# LocalElectricCircuit.net
KiCad netlist of a schematic drawn in EAGLE
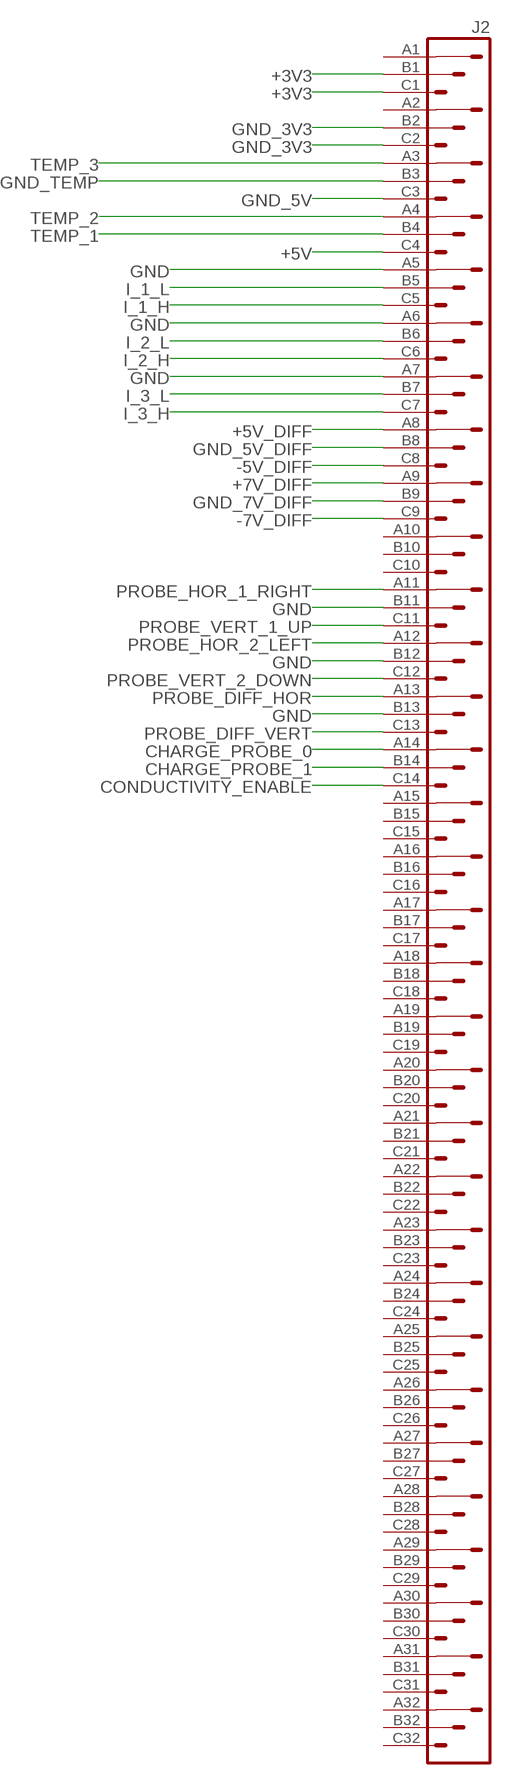
[diagram p0: schematic, sheet 1, part 1 of 2]
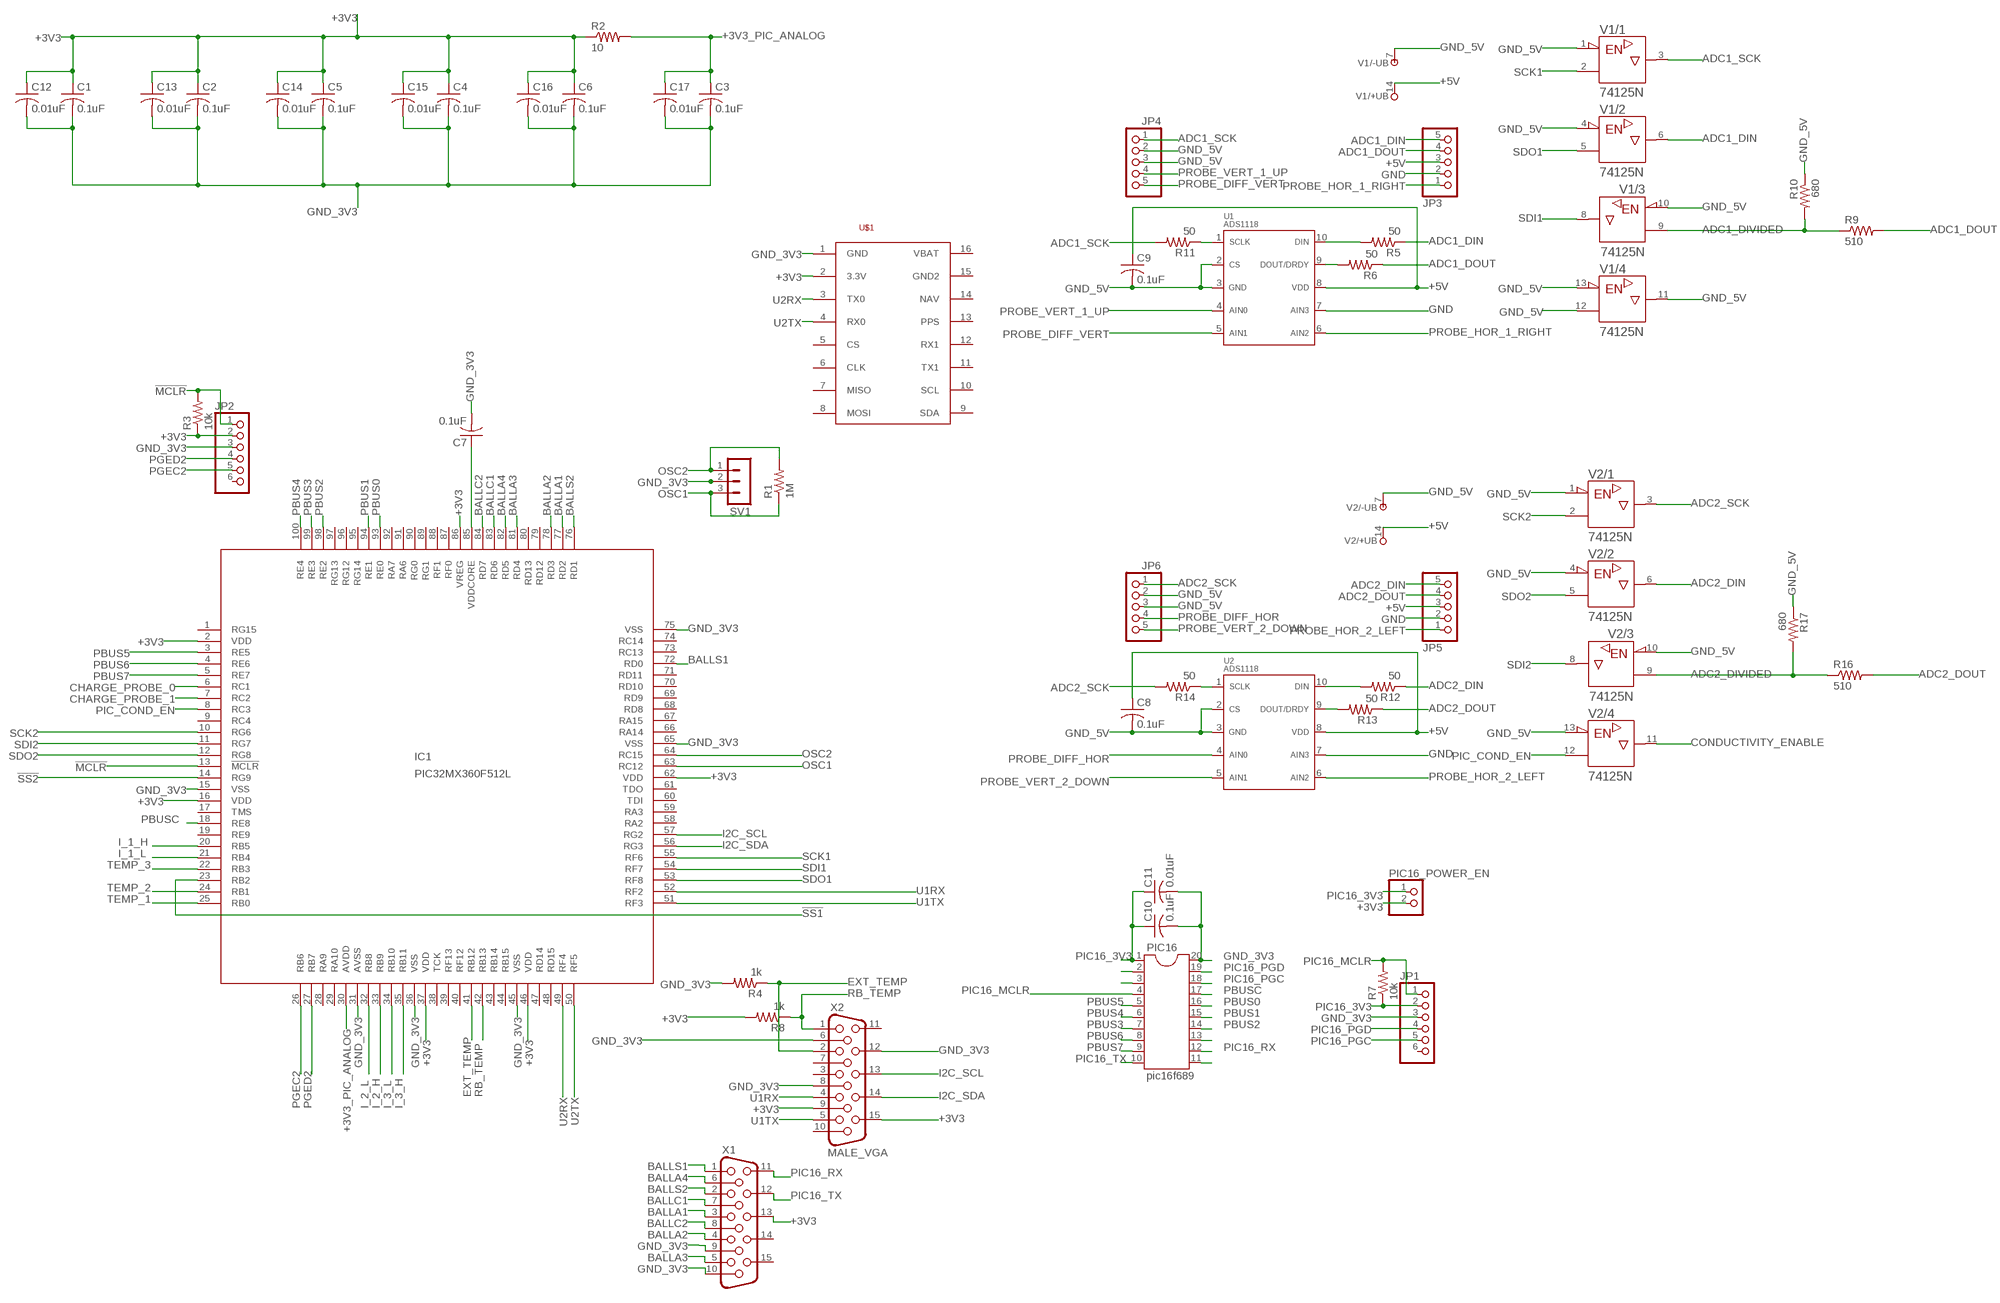
[diagram p1: schematic, sheet 1, part 2 of 2]

(export (version "E")
  (design (tool "Eeschema 10.0.6"))
  (components
    (comp (ref "C1")
      (value "0.1uF")
      (footprint "eagle-import:C1206")
      (libsource (lib "eagle-import") (part "C-USC1206"))
    )
    (comp (ref "C2")
      (value "0.1uF")
      (footprint "eagle-import:C1206")
      (libsource (lib "eagle-import") (part "C-USC1206"))
    )
    (comp (ref "C3")
      (value "0.1uF")
      (footprint "eagle-import:C1206")
      (libsource (lib "eagle-import") (part "C-USC1206"))
    )
    (comp (ref "C4")
      (value "0.1uF")
      (footprint "eagle-import:C1206")
      (libsource (lib "eagle-import") (part "C-USC1206"))
    )
    (comp (ref "C5")
      (value "0.1uF")
      (footprint "eagle-import:C1206")
      (libsource (lib "eagle-import") (part "C-USC1206"))
    )
    (comp (ref "C6")
      (value "0.1uF")
      (footprint "eagle-import:C1206")
      (libsource (lib "eagle-import") (part "C-USC1206"))
    )
    (comp (ref "C7")
      (value "0.1uF")
      (footprint "eagle-import:C1206")
      (libsource (lib "eagle-import") (part "C-USC1206"))
    )
    (comp (ref "C8")
      (value "0.1uF")
      (footprint "eagle-import:C1206")
      (libsource (lib "eagle-import") (part "C-USC1206"))
    )
    (comp (ref "C9")
      (value "0.1uF")
      (footprint "eagle-import:C1206")
      (libsource (lib "eagle-import") (part "C-USC1206"))
    )
    (comp (ref "C10")
      (value "0.1uF")
      (footprint "eagle-import:C1206")
      (libsource (lib "eagle-import") (part "C-USC1206"))
    )
    (comp (ref "C11")
      (value "0.01uF")
      (footprint "eagle-import:C1206")
      (libsource (lib "eagle-import") (part "C-USC1206"))
    )
    (comp (ref "C12")
      (value "0.01uF")
      (footprint "eagle-import:C1206")
      (libsource (lib "eagle-import") (part "C-USC1206"))
    )
    (comp (ref "C13")
      (value "0.01uF")
      (footprint "eagle-import:C1206")
      (libsource (lib "eagle-import") (part "C-USC1206"))
    )
    (comp (ref "C14")
      (value "0.01uF")
      (footprint "eagle-import:C1206")
      (libsource (lib "eagle-import") (part "C-USC1206"))
    )
    (comp (ref "C15")
      (value "0.01uF")
      (footprint "eagle-import:C1206")
      (libsource (lib "eagle-import") (part "C-USC1206"))
    )
    (comp (ref "C16")
      (value "0.01uF")
      (footprint "eagle-import:C1206")
      (libsource (lib "eagle-import") (part "C-USC1206"))
    )
    (comp (ref "C17")
      (value "0.01uF")
      (footprint "eagle-import:C1206")
      (libsource (lib "eagle-import") (part "C-USC1206"))
    )
    (comp (ref "IC1")
      (value "PIC32MX360F512L")
      (footprint "eagle-import:TQFP100")
      (libsource (lib "eagle-import") (part "PIC32MX360F512L"))
    )
    (comp (ref "J2")
      (value "VG96KB")
      (footprint "eagle-import:VG96KB")
      (libsource (lib "eagle-import") (part "VG96KB"))
    )
    (comp (ref "JP1")
      (value "PINHD-1X6")
      (footprint "eagle-import:1X06")
      (libsource (lib "eagle-import") (part "PINHD-1X6"))
    )
    (comp (ref "JP2")
      (value "PINHD-1X6")
      (footprint "eagle-import:1X06")
      (libsource (lib "eagle-import") (part "PINHD-1X6"))
    )
    (comp (ref "JP3")
      (value "PINHD-1X5")
      (footprint "eagle-import:1X05")
      (libsource (lib "eagle-import") (part "PINHD-1X5"))
    )
    (comp (ref "JP4")
      (value "PINHD-1X5")
      (footprint "eagle-import:1X05")
      (libsource (lib "eagle-import") (part "PINHD-1X5"))
    )
    (comp (ref "JP5")
      (value "PINHD-1X5")
      (footprint "eagle-import:1X05")
      (libsource (lib "eagle-import") (part "PINHD-1X5"))
    )
    (comp (ref "JP6")
      (value "PINHD-1X5")
      (footprint "eagle-import:1X05")
      (libsource (lib "eagle-import") (part "PINHD-1X5"))
    )
    (comp (ref "PIC16")
      (value "pic16f689")
      (footprint "eagle-import:DIL20")
      (libsource (lib "eagle-import") (part "DIL20"))
    )
    (comp (ref "PIC16_POWER_EN")
      (value "PINHD-1X2")
      (footprint "eagle-import:1X02")
      (libsource (lib "eagle-import") (part "PINHD-1X2"))
    )
    (comp (ref "R1")
      (value "1M")
      (footprint "eagle-import:M1206")
      (libsource (lib "eagle-import") (part "R-US_M1206"))
    )
    (comp (ref "R2")
      (value "10")
      (footprint "eagle-import:M1206")
      (libsource (lib "eagle-import") (part "R-US_M1206"))
    )
    (comp (ref "R3")
      (value "10k")
      (footprint "eagle-import:M1206")
      (libsource (lib "eagle-import") (part "R-US_M1206"))
    )
    (comp (ref "R4")
      (value "1k")
      (footprint "eagle-import:0414_15")
      (libsource (lib "eagle-import") (part "resistor_R-US_0414/15"))
    )
    (comp (ref "R5")
      (value "50")
      (footprint "eagle-import:M1206")
      (libsource (lib "eagle-import") (part "R-US_M1206"))
    )
    (comp (ref "R6")
      (value "50")
      (footprint "eagle-import:M1206")
      (libsource (lib "eagle-import") (part "R-US_M1206"))
    )
    (comp (ref "R7")
      (value "10k")
      (footprint "eagle-import:M1206")
      (libsource (lib "eagle-import") (part "R-US_M1206"))
    )
    (comp (ref "R8")
      (value "1k")
      (footprint "eagle-import:0414_15")
      (libsource (lib "eagle-import") (part "resistor_R-US_0414/15"))
    )
    (comp (ref "R9")
      (value "510")
      (footprint "eagle-import:R1206")
      (libsource (lib "eagle-import") (part "resistor_R-US_R1206"))
    )
    (comp (ref "R10")
      (value "680")
      (footprint "eagle-import:R1206")
      (libsource (lib "eagle-import") (part "resistor_R-US_R1206"))
    )
    (comp (ref "R11")
      (value "50")
      (footprint "eagle-import:M1206")
      (libsource (lib "eagle-import") (part "R-US_M1206"))
    )
    (comp (ref "R12")
      (value "50")
      (footprint "eagle-import:M1206")
      (libsource (lib "eagle-import") (part "R-US_M1206"))
    )
    (comp (ref "R13")
      (value "50")
      (footprint "eagle-import:M1206")
      (libsource (lib "eagle-import") (part "R-US_M1206"))
    )
    (comp (ref "R14")
      (value "50")
      (footprint "eagle-import:M1206")
      (libsource (lib "eagle-import") (part "R-US_M1206"))
    )
    (comp (ref "R16")
      (value "510")
      (footprint "eagle-import:R1206")
      (libsource (lib "eagle-import") (part "resistor_R-US_R1206"))
    )
    (comp (ref "R17")
      (value "680")
      (footprint "eagle-import:R1206")
      (libsource (lib "eagle-import") (part "resistor_R-US_R1206"))
    )
    (comp (ref "SV1")
      (value "MA03-1")
      (footprint "eagle-import:MA03-1")
      (libsource (lib "eagle-import") (part "MA03-1"))
    )
    (comp (ref "U$1")
      (value "SPARKFUN_VENUS_GPS_BREAKOUT")
      (footprint "eagle-import:SPARKFUN_BOARD")
      (libsource (lib "eagle-import") (part "SPARKFUN_VENUS_GPS_BREAKOUT"))
    )
    (comp (ref "U1")
      (value "ADS1118")
      (footprint "eagle-import:MSOP10")
      (libsource (lib "eagle-import") (part "ADS1118_MSOP10"))
    )
    (comp (ref "U2")
      (value "ADS1118")
      (footprint "eagle-import:MSOP10")
      (libsource (lib "eagle-import") (part "ADS1118_MSOP10"))
    )
    (comp (ref "V1")
      (value "74125N")
      (footprint "eagle-import:DIL14")
      (libsource (lib "eagle-import") (part "74125N"))
    )
    (comp (ref "V2")
      (value "74125N")
      (footprint "eagle-import:DIL14")
      (libsource (lib "eagle-import") (part "74125N"))
    )
    (comp (ref "X1")
      (value "HF15H")
      (footprint "eagle-import:HDF15H")
      (libsource (lib "eagle-import") (part "HF15H"))
    )
    (comp (ref "X2")
      (value "MALE_VGA")
      (footprint "eagle-import:MALE_PACKAGE")
      (libsource (lib "eagle-import") (part "MALE_VGA"))
    )
  )
  (nets
    (net (code "1") (name "/+3V3") (class "Default")
      (node (ref "C1") (pin "1") (pinfunction "1_1") (pintype "passive"))
      (node (ref "C12") (pin "1") (pinfunction "1_1") (pintype "passive"))
      (node (ref "C13") (pin "1") (pinfunction "1_1") (pintype "passive"))
      (node (ref "C14") (pin "1") (pinfunction "1_1") (pintype "passive"))
      (node (ref "C15") (pin "1") (pinfunction "1_1") (pintype "passive"))
      (node (ref "C16") (pin "1") (pinfunction "1_1") (pintype "passive"))
      (node (ref "C2") (pin "1") (pinfunction "1_1") (pintype "passive"))
      (node (ref "C4") (pin "1") (pinfunction "1_1") (pintype "passive"))
      (node (ref "C5") (pin "1") (pinfunction "1_1") (pintype "passive"))
      (node (ref "C6") (pin "1") (pinfunction "1_1") (pintype "passive"))
      (node (ref "IC1") (pin "16") (pinfunction "VDD_16") (pintype "power_in"))
      (node (ref "IC1") (pin "2") (pinfunction "VDD_2") (pintype "power_in"))
      (node (ref "IC1") (pin "37") (pinfunction "VDD_37") (pintype "power_in"))
      (node (ref "IC1") (pin "46") (pinfunction "VDD_46") (pintype "power_in"))
      (node (ref "IC1") (pin "62") (pinfunction "VDD_62") (pintype "power_in"))
      (node (ref "IC1") (pin "86") (pinfunction "VREG_86") (pintype "passive"))
      (node (ref "J2") (pin "B1") (pinfunction "B1_B1") (pintype "passive"))
      (node (ref "J2") (pin "C1") (pinfunction "C1_C1") (pintype "passive"))
      (node (ref "JP2") (pin "2") (pinfunction "2_2") (pintype "passive"))
      (node (ref "PIC16_POWER_EN") (pin "2") (pinfunction "2_2") (pintype "passive"))
      (node (ref "R2") (pin "1") (pinfunction "1_1") (pintype "passive"))
      (node (ref "R3") (pin "1") (pinfunction "1_1") (pintype "passive"))
      (node (ref "R8") (pin "2") (pinfunction "2_2") (pintype "passive"))
      (node (ref "U$1") (pin "2") (pinfunction "3.3V_2") (pintype "bidirectional"))
      (node (ref "X1") (pin "13") (pinfunction "13_13") (pintype "passive"))
      (node (ref "X2") (pin "15") (pinfunction "15_15") (pintype "passive"))
      (node (ref "X2") (pin "9") (pinfunction "9_9") (pintype "passive"))
    )
    (net (code "2") (name "/+3V3_PIC_ANALOG") (class "Default")
      (node (ref "C17") (pin "1") (pinfunction "1_1") (pintype "passive"))
      (node (ref "C3") (pin "1") (pinfunction "1_1") (pintype "passive"))
      (node (ref "IC1") (pin "30") (pinfunction "AVDD_30") (pintype "power_in"))
      (node (ref "R2") (pin "2") (pinfunction "2_2") (pintype "passive"))
    )
    (net (code "3") (name "/+5V") (class "Default")
      (node (ref "C8") (pin "1") (pinfunction "1_1") (pintype "passive"))
      (node (ref "C9") (pin "1") (pinfunction "1_1") (pintype "passive"))
      (node (ref "J2") (pin "C4") (pinfunction "C4_C4") (pintype "passive"))
      (node (ref "JP3") (pin "3") (pinfunction "3_3") (pintype "passive"))
      (node (ref "JP5") (pin "3") (pinfunction "3_3") (pintype "passive"))
      (node (ref "U1") (pin "8") (pinfunction "VDD_8") (pintype "bidirectional"))
      (node (ref "U2") (pin "8") (pinfunction "VDD_8") (pintype "bidirectional"))
      (node (ref "V1") (pin "14") (pinfunction "+UB_14") (pintype "power_in"))
      (node (ref "V2") (pin "14") (pinfunction "+UB_14") (pintype "power_in"))
    )
    (net (code "4") (name "/+5V_DIFF") (class "Default")
      (node (ref "J2") (pin "A8") (pinfunction "A8_A8") (pintype "passive"))
    )
    (net (code "5") (name "/+7V_DIFF") (class "Default")
      (node (ref "J2") (pin "A9") (pinfunction "A9_A9") (pintype "passive"))
    )
    (net (code "6") (name "/-5V_DIFF") (class "Default")
      (node (ref "J2") (pin "C8") (pinfunction "C8_C8") (pintype "passive"))
    )
    (net (code "7") (name "/-7V_DIFF") (class "Default")
      (node (ref "J2") (pin "C9") (pinfunction "C9_C9") (pintype "passive"))
    )
    (net (code "8") (name "/ADC1_DIN") (class "Default")
      (node (ref "JP3") (pin "5") (pinfunction "5_5") (pintype "passive"))
      (node (ref "R5") (pin "1") (pinfunction "1_1") (pintype "passive"))
      (node (ref "V1") (pin "6") (pinfunction "Y_6") (pintype "tri_state"))
    )
    (net (code "9") (name "/ADC1_DIVIDED") (class "Default")
      (node (ref "R10") (pin "2") (pinfunction "2_2") (pintype "passive"))
      (node (ref "R9") (pin "1") (pinfunction "1_1") (pintype "passive"))
      (node (ref "V1") (pin "9") (pinfunction "A_9") (pintype "input"))
    )
    (net (code "10") (name "/ADC1_DOUT") (class "Default")
      (node (ref "JP3") (pin "4") (pinfunction "4_4") (pintype "passive"))
      (node (ref "R6") (pin "1") (pinfunction "1_1") (pintype "passive"))
      (node (ref "R9") (pin "2") (pinfunction "2_2") (pintype "passive"))
    )
    (net (code "11") (name "/ADC1_SCK") (class "Default")
      (node (ref "JP4") (pin "1") (pinfunction "1_1") (pintype "passive"))
      (node (ref "R11") (pin "2") (pinfunction "2_2") (pintype "passive"))
      (node (ref "V1") (pin "3") (pinfunction "Y_3") (pintype "tri_state"))
    )
    (net (code "12") (name "/ADC2_DIN") (class "Default")
      (node (ref "JP5") (pin "5") (pinfunction "5_5") (pintype "passive"))
      (node (ref "R12") (pin "1") (pinfunction "1_1") (pintype "passive"))
      (node (ref "V2") (pin "6") (pinfunction "Y_6") (pintype "tri_state"))
    )
    (net (code "13") (name "/ADC2_DIVIDED") (class "Default")
      (node (ref "R16") (pin "1") (pinfunction "1_1") (pintype "passive"))
      (node (ref "R17") (pin "2") (pinfunction "2_2") (pintype "passive"))
      (node (ref "V2") (pin "9") (pinfunction "A_9") (pintype "input"))
    )
    (net (code "14") (name "/ADC2_DOUT") (class "Default")
      (node (ref "JP5") (pin "4") (pinfunction "4_4") (pintype "passive"))
      (node (ref "R13") (pin "1") (pinfunction "1_1") (pintype "passive"))
      (node (ref "R16") (pin "2") (pinfunction "2_2") (pintype "passive"))
    )
    (net (code "15") (name "/ADC2_SCK") (class "Default")
      (node (ref "JP6") (pin "1") (pinfunction "1_1") (pintype "passive"))
      (node (ref "R14") (pin "2") (pinfunction "2_2") (pintype "passive"))
      (node (ref "V2") (pin "3") (pinfunction "Y_3") (pintype "tri_state"))
    )
    (net (code "16") (name "/BALLA1") (class "Default")
      (node (ref "IC1") (pin "77") (pinfunction "RD2_77") (pintype "bidirectional"))
      (node (ref "X1") (pin "3") (pinfunction "3_3") (pintype "passive"))
    )
    (net (code "17") (name "/BALLA2") (class "Default")
      (node (ref "IC1") (pin "78") (pinfunction "RD3_78") (pintype "bidirectional"))
      (node (ref "X1") (pin "4") (pinfunction "4_4") (pintype "passive"))
    )
    (net (code "18") (name "/BALLA3") (class "Default")
      (node (ref "IC1") (pin "81") (pinfunction "RD4_81") (pintype "bidirectional"))
      (node (ref "X1") (pin "5") (pinfunction "5_5") (pintype "passive"))
    )
    (net (code "19") (name "/BALLA4") (class "Default")
      (node (ref "IC1") (pin "82") (pinfunction "RD5_82") (pintype "bidirectional"))
      (node (ref "X1") (pin "6") (pinfunction "6_6") (pintype "passive"))
    )
    (net (code "20") (name "/BALLC1") (class "Default")
      (node (ref "IC1") (pin "83") (pinfunction "RD6_83") (pintype "bidirectional"))
      (node (ref "X1") (pin "7") (pinfunction "7_7") (pintype "passive"))
    )
    (net (code "21") (name "/BALLC2") (class "Default")
      (node (ref "IC1") (pin "84") (pinfunction "RD7_84") (pintype "bidirectional"))
      (node (ref "X1") (pin "8") (pinfunction "8_8") (pintype "passive"))
    )
    (net (code "22") (name "/BALLS1") (class "Default")
      (node (ref "IC1") (pin "72") (pinfunction "RD0_72") (pintype "bidirectional"))
      (node (ref "X1") (pin "1") (pinfunction "1_1") (pintype "passive"))
    )
    (net (code "23") (name "/BALLS2") (class "Default")
      (node (ref "IC1") (pin "76") (pinfunction "RD1_76") (pintype "bidirectional"))
      (node (ref "X1") (pin "2") (pinfunction "2_2") (pintype "passive"))
    )
    (net (code "24") (name "/CHARGE_PROBE_0") (class "Default")
      (node (ref "IC1") (pin "6") (pinfunction "RC1_6") (pintype "bidirectional"))
      (node (ref "J2") (pin "A14") (pinfunction "A14_A14") (pintype "passive"))
    )
    (net (code "25") (name "/CHARGE_PROBE_1") (class "Default")
      (node (ref "IC1") (pin "7") (pinfunction "RC2_7") (pintype "bidirectional"))
      (node (ref "J2") (pin "B14") (pinfunction "B14_B14") (pintype "passive"))
    )
    (net (code "26") (name "/CONDUCTIVITY_ENABLE") (class "Default")
      (node (ref "J2") (pin "C14") (pinfunction "C14_C14") (pintype "passive"))
      (node (ref "V2") (pin "11") (pinfunction "Y_11") (pintype "tri_state"))
    )
    (net (code "27") (name "/EXT_TEMP") (class "Default")
      (node (ref "IC1") (pin "41") (pinfunction "RB12_41") (pintype "bidirectional"))
      (node (ref "R4") (pin "1") (pinfunction "1_1") (pintype "passive"))
      (node (ref "X2") (pin "2") (pinfunction "2_2") (pintype "passive"))
    )
    (net (code "28") (name "/GND") (class "Default")
      (node (ref "J2") (pin "A5") (pinfunction "A5_A5") (pintype "passive"))
      (node (ref "J2") (pin "A6") (pinfunction "A6_A6") (pintype "passive"))
      (node (ref "J2") (pin "A7") (pinfunction "A7_A7") (pintype "passive"))
      (node (ref "J2") (pin "B11") (pinfunction "B11_B11") (pintype "passive"))
      (node (ref "J2") (pin "B12") (pinfunction "B12_B12") (pintype "passive"))
      (node (ref "J2") (pin "B13") (pinfunction "B13_B13") (pintype "passive"))
      (node (ref "JP3") (pin "2") (pinfunction "2_2") (pintype "passive"))
      (node (ref "JP5") (pin "2") (pinfunction "2_2") (pintype "passive"))
      (node (ref "U1") (pin "7") (pinfunction "AIN3_7") (pintype "bidirectional"))
      (node (ref "U2") (pin "7") (pinfunction "AIN3_7") (pintype "bidirectional"))
    )
    (net (code "29") (name "/GND_3V3") (class "Default")
      (node (ref "C1") (pin "2") (pinfunction "2_2") (pintype "passive"))
      (node (ref "C10") (pin "2") (pinfunction "2_2") (pintype "passive"))
      (node (ref "C11") (pin "2") (pinfunction "2_2") (pintype "passive"))
      (node (ref "C12") (pin "2") (pinfunction "2_2") (pintype "passive"))
      (node (ref "C13") (pin "2") (pinfunction "2_2") (pintype "passive"))
      (node (ref "C14") (pin "2") (pinfunction "2_2") (pintype "passive"))
      (node (ref "C15") (pin "2") (pinfunction "2_2") (pintype "passive"))
      (node (ref "C16") (pin "2") (pinfunction "2_2") (pintype "passive"))
      (node (ref "C17") (pin "2") (pinfunction "2_2") (pintype "passive"))
      (node (ref "C2") (pin "2") (pinfunction "2_2") (pintype "passive"))
      (node (ref "C3") (pin "2") (pinfunction "2_2") (pintype "passive"))
      (node (ref "C4") (pin "2") (pinfunction "2_2") (pintype "passive"))
      (node (ref "C5") (pin "2") (pinfunction "2_2") (pintype "passive"))
      (node (ref "C6") (pin "2") (pinfunction "2_2") (pintype "passive"))
      (node (ref "C7") (pin "2") (pinfunction "2_2") (pintype "passive"))
      (node (ref "IC1") (pin "15") (pinfunction "VSS_15") (pintype "power_in"))
      (node (ref "IC1") (pin "31") (pinfunction "AVSS_31") (pintype "power_in"))
      (node (ref "IC1") (pin "36") (pinfunction "VSS_36") (pintype "power_in"))
      (node (ref "IC1") (pin "45") (pinfunction "VSS_45") (pintype "power_in"))
      (node (ref "IC1") (pin "65") (pinfunction "VSS_65") (pintype "power_in"))
      (node (ref "IC1") (pin "75") (pinfunction "VSS_75") (pintype "power_in"))
      (node (ref "J2") (pin "B2") (pinfunction "B2_B2") (pintype "passive"))
      (node (ref "J2") (pin "C2") (pinfunction "C2_C2") (pintype "passive"))
      (node (ref "JP1") (pin "3") (pinfunction "3_3") (pintype "passive"))
      (node (ref "JP2") (pin "3") (pinfunction "3_3") (pintype "passive"))
      (node (ref "PIC16") (pin "20") (pinfunction "20_20") (pintype "passive"))
      (node (ref "R4") (pin "2") (pinfunction "2_2") (pintype "passive"))
      (node (ref "SV1") (pin "2") (pinfunction "2_2") (pintype "passive"))
      (node (ref "U$1") (pin "1") (pinfunction "GND_1") (pintype "bidirectional"))
      (node (ref "X1") (pin "10") (pinfunction "10_10") (pintype "passive"))
      (node (ref "X1") (pin "9") (pinfunction "9_9") (pintype "passive"))
      (node (ref "X2") (pin "12") (pinfunction "12_12") (pintype "passive"))
      (node (ref "X2") (pin "6") (pinfunction "6_6") (pintype "passive"))
      (node (ref "X2") (pin "8") (pinfunction "8_8") (pintype "passive"))
    )
    (net (code "30") (name "/GND_5V") (class "Default")
      (node (ref "C8") (pin "2") (pinfunction "2_2") (pintype "passive"))
      (node (ref "C9") (pin "2") (pinfunction "2_2") (pintype "passive"))
      (node (ref "J2") (pin "C3") (pinfunction "C3_C3") (pintype "passive"))
      (node (ref "JP4") (pin "2") (pinfunction "2_2") (pintype "passive"))
      (node (ref "JP4") (pin "3") (pinfunction "3_3") (pintype "passive"))
      (node (ref "JP6") (pin "2") (pinfunction "2_2") (pintype "passive"))
      (node (ref "JP6") (pin "3") (pinfunction "3_3") (pintype "passive"))
      (node (ref "R10") (pin "1") (pinfunction "1_1") (pintype "passive"))
      (node (ref "R17") (pin "1") (pinfunction "1_1") (pintype "passive"))
      (node (ref "U1") (pin "2") (pinfunction "CS_2") (pintype "bidirectional"))
      (node (ref "U1") (pin "3") (pinfunction "GND_3") (pintype "bidirectional"))
      (node (ref "U2") (pin "2") (pinfunction "CS_2") (pintype "bidirectional"))
      (node (ref "U2") (pin "3") (pinfunction "GND_3") (pintype "bidirectional"))
      (node (ref "V1") (pin "1") (pinfunction "~{G}_1") (pintype "input"))
      (node (ref "V1") (pin "10") (pinfunction "~{G}_10") (pintype "input"))
      (node (ref "V1") (pin "11") (pinfunction "Y_11") (pintype "tri_state"))
      (node (ref "V1") (pin "12") (pinfunction "A_12") (pintype "input"))
      (node (ref "V1") (pin "13") (pinfunction "~{G}_13") (pintype "input"))
      (node (ref "V1") (pin "4") (pinfunction "~{G}_4") (pintype "input"))
      (node (ref "V1") (pin "7") (pinfunction "-UB_7") (pintype "power_in"))
      (node (ref "V2") (pin "1") (pinfunction "~{G}_1") (pintype "input"))
      (node (ref "V2") (pin "10") (pinfunction "~{G}_10") (pintype "input"))
      (node (ref "V2") (pin "13") (pinfunction "~{G}_13") (pintype "input"))
      (node (ref "V2") (pin "4") (pinfunction "~{G}_4") (pintype "input"))
      (node (ref "V2") (pin "7") (pinfunction "-UB_7") (pintype "power_in"))
    )
    (net (code "31") (name "/GND_5V_DIFF") (class "Default")
      (node (ref "J2") (pin "B8") (pinfunction "B8_B8") (pintype "passive"))
    )
    (net (code "32") (name "/GND_7V_DIFF") (class "Default")
      (node (ref "J2") (pin "B9") (pinfunction "B9_B9") (pintype "passive"))
    )
    (net (code "33") (name "/GND_TEMP") (class "Default")
      (node (ref "J2") (pin "B3") (pinfunction "B3_B3") (pintype "passive"))
    )
    (net (code "34") (name "/I2C_SCL") (class "Default")
      (node (ref "IC1") (pin "57") (pinfunction "RG2_57") (pintype "bidirectional"))
      (node (ref "X2") (pin "13") (pinfunction "13_13") (pintype "passive"))
    )
    (net (code "35") (name "/I2C_SDA") (class "Default")
      (node (ref "IC1") (pin "56") (pinfunction "RG3_56") (pintype "bidirectional"))
      (node (ref "X2") (pin "14") (pinfunction "14_14") (pintype "passive"))
    )
    (net (code "36") (name "/I_1_H") (class "Default")
      (node (ref "IC1") (pin "20") (pinfunction "RB5_20") (pintype "bidirectional"))
      (node (ref "J2") (pin "C5") (pinfunction "C5_C5") (pintype "passive"))
    )
    (net (code "37") (name "/I_1_L") (class "Default")
      (node (ref "IC1") (pin "21") (pinfunction "RB4_21") (pintype "bidirectional"))
      (node (ref "J2") (pin "B5") (pinfunction "B5_B5") (pintype "passive"))
    )
    (net (code "38") (name "/I_2_H") (class "Default")
      (node (ref "IC1") (pin "33") (pinfunction "RB9_33") (pintype "bidirectional"))
      (node (ref "J2") (pin "C6") (pinfunction "C6_C6") (pintype "passive"))
    )
    (net (code "39") (name "/I_2_L") (class "Default")
      (node (ref "IC1") (pin "32") (pinfunction "RB8_32") (pintype "bidirectional"))
      (node (ref "J2") (pin "B6") (pinfunction "B6_B6") (pintype "passive"))
    )
    (net (code "40") (name "/I_3_H") (class "Default")
      (node (ref "IC1") (pin "35") (pinfunction "RB11_35") (pintype "bidirectional"))
      (node (ref "J2") (pin "C7") (pinfunction "C7_C7") (pintype "passive"))
    )
    (net (code "41") (name "/I_3_L") (class "Default")
      (node (ref "IC1") (pin "34") (pinfunction "RB10_34") (pintype "bidirectional"))
      (node (ref "J2") (pin "B7") (pinfunction "B7_B7") (pintype "passive"))
    )
    (net (code "42") (name "/OSC1") (class "Default")
      (node (ref "IC1") (pin "63") (pinfunction "RC12_63") (pintype "bidirectional"))
      (node (ref "R1") (pin "1") (pinfunction "1_1") (pintype "passive"))
      (node (ref "SV1") (pin "3") (pinfunction "3_3") (pintype "passive"))
    )
    (net (code "43") (name "/OSC2") (class "Default")
      (node (ref "IC1") (pin "64") (pinfunction "RC15_64") (pintype "bidirectional"))
      (node (ref "R1") (pin "2") (pinfunction "2_2") (pintype "passive"))
      (node (ref "SV1") (pin "1") (pinfunction "1_1") (pintype "passive"))
    )
    (net (code "44") (name "/PBUS0") (class "Default")
      (node (ref "IC1") (pin "93") (pinfunction "RE0_93") (pintype "bidirectional"))
      (node (ref "PIC16") (pin "16") (pinfunction "16_16") (pintype "passive"))
    )
    (net (code "45") (name "/PBUS1") (class "Default")
      (node (ref "IC1") (pin "94") (pinfunction "RE1_94") (pintype "bidirectional"))
      (node (ref "PIC16") (pin "15") (pinfunction "15_15") (pintype "passive"))
    )
    (net (code "46") (name "/PBUS2") (class "Default")
      (node (ref "IC1") (pin "98") (pinfunction "RE2_98") (pintype "bidirectional"))
      (node (ref "PIC16") (pin "14") (pinfunction "14_14") (pintype "passive"))
    )
    (net (code "47") (name "/PBUS3") (class "Default")
      (node (ref "IC1") (pin "99") (pinfunction "RE3_99") (pintype "bidirectional"))
      (node (ref "PIC16") (pin "7") (pinfunction "7_7") (pintype "passive"))
    )
    (net (code "48") (name "/PBUS4") (class "Default")
      (node (ref "IC1") (pin "100") (pinfunction "RE4_100") (pintype "bidirectional"))
      (node (ref "PIC16") (pin "6") (pinfunction "6_6") (pintype "passive"))
    )
    (net (code "49") (name "/PBUS5") (class "Default")
      (node (ref "IC1") (pin "3") (pinfunction "RE5_3") (pintype "bidirectional"))
      (node (ref "PIC16") (pin "5") (pinfunction "5_5") (pintype "passive"))
    )
    (net (code "50") (name "/PBUS6") (class "Default")
      (node (ref "IC1") (pin "4") (pinfunction "RE6_4") (pintype "bidirectional"))
      (node (ref "PIC16") (pin "8") (pinfunction "8_8") (pintype "passive"))
    )
    (net (code "51") (name "/PBUS7") (class "Default")
      (node (ref "IC1") (pin "5") (pinfunction "RE7_5") (pintype "bidirectional"))
      (node (ref "PIC16") (pin "9") (pinfunction "9_9") (pintype "passive"))
    )
    (net (code "52") (name "/PBUSC") (class "Default")
      (node (ref "IC1") (pin "18") (pinfunction "RE8_18") (pintype "bidirectional"))
      (node (ref "PIC16") (pin "17") (pinfunction "17_17") (pintype "passive"))
    )
    (net (code "53") (name "/PGEC2") (class "Default")
      (node (ref "IC1") (pin "26") (pinfunction "RB6_26") (pintype "bidirectional"))
      (node (ref "JP2") (pin "5") (pinfunction "5_5") (pintype "passive"))
    )
    (net (code "54") (name "/PGED2") (class "Default")
      (node (ref "IC1") (pin "27") (pinfunction "RB7_27") (pintype "bidirectional"))
      (node (ref "JP2") (pin "4") (pinfunction "4_4") (pintype "passive"))
    )
    (net (code "55") (name "/PIC16_3V3") (class "Default")
      (node (ref "C10") (pin "1") (pinfunction "1_1") (pintype "passive"))
      (node (ref "C11") (pin "1") (pinfunction "1_1") (pintype "passive"))
      (node (ref "JP1") (pin "2") (pinfunction "2_2") (pintype "passive"))
      (node (ref "PIC16") (pin "1") (pinfunction "1_1") (pintype "passive"))
      (node (ref "PIC16_POWER_EN") (pin "1") (pinfunction "1_1") (pintype "passive"))
      (node (ref "R7") (pin "1") (pinfunction "1_1") (pintype "passive"))
    )
    (net (code "56") (name "/PIC16_MCLR") (class "Default")
      (node (ref "JP1") (pin "1") (pinfunction "1_1") (pintype "passive"))
      (node (ref "PIC16") (pin "4") (pinfunction "4_4") (pintype "passive"))
      (node (ref "R7") (pin "2") (pinfunction "2_2") (pintype "passive"))
    )
    (net (code "57") (name "/PIC16_PGC") (class "Default")
      (node (ref "JP1") (pin "5") (pinfunction "5_5") (pintype "passive"))
      (node (ref "PIC16") (pin "18") (pinfunction "18_18") (pintype "passive"))
    )
    (net (code "58") (name "/PIC16_PGD") (class "Default")
      (node (ref "JP1") (pin "4") (pinfunction "4_4") (pintype "passive"))
      (node (ref "PIC16") (pin "19") (pinfunction "19_19") (pintype "passive"))
    )
    (net (code "59") (name "/PIC16_RX") (class "Default")
      (node (ref "PIC16") (pin "12") (pinfunction "12_12") (pintype "passive"))
      (node (ref "X1") (pin "11") (pinfunction "11_11") (pintype "passive"))
    )
    (net (code "60") (name "/PIC16_TX") (class "Default")
      (node (ref "PIC16") (pin "10") (pinfunction "10_10") (pintype "passive"))
      (node (ref "X1") (pin "12") (pinfunction "12_12") (pintype "passive"))
    )
    (net (code "61") (name "/PIC_COND_EN") (class "Default")
      (node (ref "IC1") (pin "8") (pinfunction "RC3_8") (pintype "bidirectional"))
      (node (ref "V2") (pin "12") (pinfunction "A_12") (pintype "input"))
    )
    (net (code "62") (name "/PROBE_DIFF_HOR") (class "Default")
      (node (ref "J2") (pin "A13") (pinfunction "A13_A13") (pintype "passive"))
      (node (ref "JP6") (pin "4") (pinfunction "4_4") (pintype "passive"))
      (node (ref "U2") (pin "4") (pinfunction "AIN0_4") (pintype "bidirectional"))
    )
    (net (code "63") (name "/PROBE_DIFF_VERT") (class "Default")
      (node (ref "J2") (pin "C13") (pinfunction "C13_C13") (pintype "passive"))
      (node (ref "JP4") (pin "5") (pinfunction "5_5") (pintype "passive"))
      (node (ref "U1") (pin "5") (pinfunction "AIN1_5") (pintype "bidirectional"))
    )
    (net (code "64") (name "/PROBE_HOR_1_RIGHT") (class "Default")
      (node (ref "J2") (pin "A11") (pinfunction "A11_A11") (pintype "passive"))
      (node (ref "JP3") (pin "1") (pinfunction "1_1") (pintype "passive"))
      (node (ref "U1") (pin "6") (pinfunction "AIN2_6") (pintype "bidirectional"))
    )
    (net (code "65") (name "/PROBE_HOR_2_LEFT") (class "Default")
      (node (ref "J2") (pin "A12") (pinfunction "A12_A12") (pintype "passive"))
      (node (ref "JP5") (pin "1") (pinfunction "1_1") (pintype "passive"))
      (node (ref "U2") (pin "6") (pinfunction "AIN2_6") (pintype "bidirectional"))
    )
    (net (code "66") (name "/PROBE_VERT_1_UP") (class "Default")
      (node (ref "J2") (pin "C11") (pinfunction "C11_C11") (pintype "passive"))
      (node (ref "JP4") (pin "4") (pinfunction "4_4") (pintype "passive"))
      (node (ref "U1") (pin "4") (pinfunction "AIN0_4") (pintype "bidirectional"))
    )
    (net (code "67") (name "/PROBE_VERT_2_DOWN") (class "Default")
      (node (ref "J2") (pin "C12") (pinfunction "C12_C12") (pintype "passive"))
      (node (ref "JP6") (pin "5") (pinfunction "5_5") (pintype "passive"))
      (node (ref "U2") (pin "5") (pinfunction "AIN1_5") (pintype "bidirectional"))
    )
    (net (code "68") (name "/RB_TEMP") (class "Default")
      (node (ref "IC1") (pin "42") (pinfunction "RB13_42") (pintype "bidirectional"))
      (node (ref "R8") (pin "1") (pinfunction "1_1") (pintype "passive"))
      (node (ref "X2") (pin "1") (pinfunction "1_1") (pintype "passive"))
    )
    (net (code "69") (name "/SCK1") (class "Default")
      (node (ref "IC1") (pin "55") (pinfunction "RF6_55") (pintype "bidirectional"))
      (node (ref "V1") (pin "2") (pinfunction "A_2") (pintype "input"))
    )
    (net (code "70") (name "/SCK2") (class "Default")
      (node (ref "IC1") (pin "10") (pinfunction "RG6_10") (pintype "bidirectional"))
      (node (ref "V2") (pin "2") (pinfunction "A_2") (pintype "input"))
    )
    (net (code "71") (name "/SDI1") (class "Default")
      (node (ref "IC1") (pin "54") (pinfunction "RF7_54") (pintype "bidirectional"))
      (node (ref "V1") (pin "8") (pinfunction "Y_8") (pintype "tri_state"))
    )
    (net (code "72") (name "/SDI2") (class "Default")
      (node (ref "IC1") (pin "11") (pinfunction "RG7_11") (pintype "bidirectional"))
      (node (ref "V2") (pin "8") (pinfunction "Y_8") (pintype "tri_state"))
    )
    (net (code "73") (name "/SDO1") (class "Default")
      (node (ref "IC1") (pin "53") (pinfunction "RF8_53") (pintype "bidirectional"))
      (node (ref "V1") (pin "5") (pinfunction "A_5") (pintype "input"))
    )
    (net (code "74") (name "/SDO2") (class "Default")
      (node (ref "IC1") (pin "12") (pinfunction "RG8_12") (pintype "bidirectional"))
      (node (ref "V2") (pin "5") (pinfunction "A_5") (pintype "input"))
    )
    (net (code "75") (name "/TEMP_1") (class "Default")
      (node (ref "IC1") (pin "25") (pinfunction "RB0_25") (pintype "bidirectional"))
      (node (ref "J2") (pin "B4") (pinfunction "B4_B4") (pintype "passive"))
    )
    (net (code "76") (name "/TEMP_2") (class "Default")
      (node (ref "IC1") (pin "24") (pinfunction "RB1_24") (pintype "bidirectional"))
      (node (ref "J2") (pin "A4") (pinfunction "A4_A4") (pintype "passive"))
    )
    (net (code "77") (name "/TEMP_3") (class "Default")
      (node (ref "IC1") (pin "22") (pinfunction "RB3_22") (pintype "bidirectional"))
      (node (ref "J2") (pin "A3") (pinfunction "A3_A3") (pintype "passive"))
    )
    (net (code "78") (name "/U1RX") (class "Default")
      (node (ref "IC1") (pin "52") (pinfunction "RF2_52") (pintype "bidirectional"))
      (node (ref "X2") (pin "4") (pinfunction "4_4") (pintype "passive"))
    )
    (net (code "79") (name "/U1TX") (class "Default")
      (node (ref "IC1") (pin "51") (pinfunction "RF3_51") (pintype "bidirectional"))
      (node (ref "X2") (pin "5") (pinfunction "5_5") (pintype "passive"))
    )
    (net (code "80") (name "/U2RX") (class "Default")
      (node (ref "IC1") (pin "49") (pinfunction "RF4_49") (pintype "bidirectional"))
      (node (ref "U$1") (pin "3") (pinfunction "TX0_3") (pintype "bidirectional"))
    )
    (net (code "81") (name "/U2TX") (class "Default")
      (node (ref "IC1") (pin "50") (pinfunction "RF5_50") (pintype "bidirectional"))
      (node (ref "U$1") (pin "4") (pinfunction "RX0_4") (pintype "bidirectional"))
    )
    (net (code "82") (name "/~{MCLR}") (class "Default")
      (node (ref "IC1") (pin "13") (pinfunction "~{MCLR}_13") (pintype "input"))
      (node (ref "JP2") (pin "1") (pinfunction "1_1") (pintype "passive"))
      (node (ref "R3") (pin "2") (pinfunction "2_2") (pintype "passive"))
    )
    (net (code "83") (name "/~{SS1}") (class "Default")
      (node (ref "IC1") (pin "23") (pinfunction "RB2_23") (pintype "bidirectional"))
    )
    (net (code "84") (name "/~{SS2}") (class "Default")
      (node (ref "IC1") (pin "14") (pinfunction "RG9_14") (pintype "bidirectional"))
    )
    (net (code "85") (name "Net-(IC1-VDDCORE)") (class "Default")
      (node (ref "C7") (pin "1") (pinfunction "1_1") (pintype "passive"))
      (node (ref "IC1") (pin "85") (pinfunction "VDDCORE_85") (pintype "power_in"))
    )
    (net (code "86") (name "Net-(U1-DIN)") (class "Default")
      (node (ref "R5") (pin "2") (pinfunction "2_2") (pintype "passive"))
      (node (ref "U1") (pin "10") (pinfunction "DIN_10") (pintype "bidirectional"))
    )
    (net (code "87") (name "Net-(U1-DOUT{slash}DRDY)") (class "Default")
      (node (ref "R6") (pin "2") (pinfunction "2_2") (pintype "passive"))
      (node (ref "U1") (pin "9") (pinfunction "DOUT/DRDY_9") (pintype "bidirectional"))
    )
    (net (code "88") (name "Net-(U1-SCLK)") (class "Default")
      (node (ref "R11") (pin "1") (pinfunction "1_1") (pintype "passive"))
      (node (ref "U1") (pin "1") (pinfunction "SCLK_1") (pintype "bidirectional"))
    )
    (net (code "89") (name "Net-(U2-DIN)") (class "Default")
      (node (ref "R12") (pin "2") (pinfunction "2_2") (pintype "passive"))
      (node (ref "U2") (pin "10") (pinfunction "DIN_10") (pintype "bidirectional"))
    )
    (net (code "90") (name "Net-(U2-DOUT{slash}DRDY)") (class "Default")
      (node (ref "R13") (pin "2") (pinfunction "2_2") (pintype "passive"))
      (node (ref "U2") (pin "9") (pinfunction "DOUT/DRDY_9") (pintype "bidirectional"))
    )
    (net (code "91") (name "Net-(U2-SCLK)") (class "Default")
      (node (ref "R14") (pin "1") (pinfunction "1_1") (pintype "passive"))
      (node (ref "U2") (pin "1") (pinfunction "SCLK_1") (pintype "bidirectional"))
    )
    (net (code "92") (name "unconnected-(IC1-RA2-Pad58)") (class "Default")
      (node (ref "IC1") (pin "58") (pinfunction "RA2_58") (pintype "bidirectional"))
    )
    (net (code "93") (name "unconnected-(IC1-RA3-Pad59)") (class "Default")
      (node (ref "IC1") (pin "59") (pinfunction "RA3_59") (pintype "bidirectional"))
    )
    (net (code "94") (name "unconnected-(IC1-RA6-Pad91)") (class "Default")
      (node (ref "IC1") (pin "91") (pinfunction "RA6_91") (pintype "bidirectional"))
    )
    (net (code "95") (name "unconnected-(IC1-RA7-Pad92)") (class "Default")
      (node (ref "IC1") (pin "92") (pinfunction "RA7_92") (pintype "bidirectional"))
    )
    (net (code "96") (name "unconnected-(IC1-RA9-Pad28)") (class "Default")
      (node (ref "IC1") (pin "28") (pinfunction "RA9_28") (pintype "bidirectional"))
    )
    (net (code "97") (name "unconnected-(IC1-RA10-Pad29)") (class "Default")
      (node (ref "IC1") (pin "29") (pinfunction "RA10_29") (pintype "bidirectional"))
    )
    (net (code "98") (name "unconnected-(IC1-RA14-Pad66)") (class "Default")
      (node (ref "IC1") (pin "66") (pinfunction "RA14_66") (pintype "bidirectional"))
    )
    (net (code "99") (name "unconnected-(IC1-RA15-Pad67)") (class "Default")
      (node (ref "IC1") (pin "67") (pinfunction "RA15_67") (pintype "bidirectional"))
    )
    (net (code "100") (name "unconnected-(IC1-RB14-Pad43)") (class "Default")
      (node (ref "IC1") (pin "43") (pinfunction "RB14_43") (pintype "bidirectional"))
    )
    (net (code "101") (name "unconnected-(IC1-RB15-Pad44)") (class "Default")
      (node (ref "IC1") (pin "44") (pinfunction "RB15_44") (pintype "bidirectional"))
    )
    (net (code "102") (name "unconnected-(IC1-RC4-Pad9)") (class "Default")
      (node (ref "IC1") (pin "9") (pinfunction "RC4_9") (pintype "bidirectional"))
    )
    (net (code "103") (name "unconnected-(IC1-RC13-Pad73)") (class "Default")
      (node (ref "IC1") (pin "73") (pinfunction "RC13_73") (pintype "bidirectional"))
    )
    (net (code "104") (name "unconnected-(IC1-RC14-Pad74)") (class "Default")
      (node (ref "IC1") (pin "74") (pinfunction "RC14_74") (pintype "bidirectional"))
    )
    (net (code "105") (name "unconnected-(IC1-RD8-Pad68)") (class "Default")
      (node (ref "IC1") (pin "68") (pinfunction "RD8_68") (pintype "bidirectional"))
    )
    (net (code "106") (name "unconnected-(IC1-RD9-Pad69)") (class "Default")
      (node (ref "IC1") (pin "69") (pinfunction "RD9_69") (pintype "bidirectional"))
    )
    (net (code "107") (name "unconnected-(IC1-RD10-Pad70)") (class "Default")
      (node (ref "IC1") (pin "70") (pinfunction "RD10_70") (pintype "bidirectional"))
    )
    (net (code "108") (name "unconnected-(IC1-RD11-Pad71)") (class "Default")
      (node (ref "IC1") (pin "71") (pinfunction "RD11_71") (pintype "bidirectional"))
    )
    (net (code "109") (name "unconnected-(IC1-RD12-Pad79)") (class "Default")
      (node (ref "IC1") (pin "79") (pinfunction "RD12_79") (pintype "bidirectional"))
    )
    (net (code "110") (name "unconnected-(IC1-RD13-Pad80)") (class "Default")
      (node (ref "IC1") (pin "80") (pinfunction "RD13_80") (pintype "bidirectional"))
    )
    (net (code "111") (name "unconnected-(IC1-RD14-Pad47)") (class "Default")
      (node (ref "IC1") (pin "47") (pinfunction "RD14_47") (pintype "bidirectional"))
    )
    (net (code "112") (name "unconnected-(IC1-RD15-Pad48)") (class "Default")
      (node (ref "IC1") (pin "48") (pinfunction "RD15_48") (pintype "bidirectional"))
    )
    (net (code "113") (name "unconnected-(IC1-RE9-Pad19)") (class "Default")
      (node (ref "IC1") (pin "19") (pinfunction "RE9_19") (pintype "bidirectional"))
    )
    (net (code "114") (name "unconnected-(IC1-RF0-Pad87)") (class "Default")
      (node (ref "IC1") (pin "87") (pinfunction "RF0_87") (pintype "bidirectional"))
    )
    (net (code "115") (name "unconnected-(IC1-RF1-Pad88)") (class "Default")
      (node (ref "IC1") (pin "88") (pinfunction "RF1_88") (pintype "bidirectional"))
    )
    (net (code "116") (name "unconnected-(IC1-RF12-Pad40)") (class "Default")
      (node (ref "IC1") (pin "40") (pinfunction "RF12_40") (pintype "bidirectional"))
    )
    (net (code "117") (name "unconnected-(IC1-RF13-Pad39)") (class "Default")
      (node (ref "IC1") (pin "39") (pinfunction "RF13_39") (pintype "bidirectional"))
    )
    (net (code "118") (name "unconnected-(IC1-RG0-Pad90)") (class "Default")
      (node (ref "IC1") (pin "90") (pinfunction "RG0_90") (pintype "bidirectional"))
    )
    (net (code "119") (name "unconnected-(IC1-RG1-Pad89)") (class "Default")
      (node (ref "IC1") (pin "89") (pinfunction "RG1_89") (pintype "bidirectional"))
    )
    (net (code "120") (name "unconnected-(IC1-RG12-Pad96)") (class "Default")
      (node (ref "IC1") (pin "96") (pinfunction "RG12_96") (pintype "bidirectional"))
    )
    (net (code "121") (name "unconnected-(IC1-RG13-Pad97)") (class "Default")
      (node (ref "IC1") (pin "97") (pinfunction "RG13_97") (pintype "bidirectional"))
    )
    (net (code "122") (name "unconnected-(IC1-RG14-Pad95)") (class "Default")
      (node (ref "IC1") (pin "95") (pinfunction "RG14_95") (pintype "bidirectional"))
    )
    (net (code "123") (name "unconnected-(IC1-RG15-Pad1)") (class "Default")
      (node (ref "IC1") (pin "1") (pinfunction "RG15_1") (pintype "bidirectional"))
    )
    (net (code "124") (name "unconnected-(IC1-TCK-Pad38)") (class "Default")
      (node (ref "IC1") (pin "38") (pinfunction "TCK_38") (pintype "input"))
    )
    (net (code "125") (name "unconnected-(IC1-TDI-Pad60)") (class "Default")
      (node (ref "IC1") (pin "60") (pinfunction "TDI_60") (pintype "input"))
    )
    (net (code "126") (name "unconnected-(IC1-TDO-Pad61)") (class "Default")
      (node (ref "IC1") (pin "61") (pinfunction "TDO_61") (pintype "output"))
    )
    (net (code "127") (name "unconnected-(IC1-TMS-Pad17)") (class "Default")
      (node (ref "IC1") (pin "17") (pinfunction "TMS_17") (pintype "input"))
    )
    (net (code "128") (name "unconnected-(J2-PadA1)") (class "Default")
      (node (ref "J2") (pin "A1") (pinfunction "A1_A1") (pintype "passive"))
    )
    (net (code "129") (name "unconnected-(J2-PadA2)") (class "Default")
      (node (ref "J2") (pin "A2") (pinfunction "A2_A2") (pintype "passive"))
    )
    (net (code "130") (name "unconnected-(J2-PadA10)") (class "Default")
      (node (ref "J2") (pin "A10") (pinfunction "A10_A10") (pintype "passive"))
    )
    (net (code "131") (name "unconnected-(J2-PadA15)") (class "Default")
      (node (ref "J2") (pin "A15") (pinfunction "A15_A15") (pintype "passive"))
    )
    (net (code "132") (name "unconnected-(J2-PadA16)") (class "Default")
      (node (ref "J2") (pin "A16") (pinfunction "A16_A16") (pintype "passive"))
    )
    (net (code "133") (name "unconnected-(J2-PadA17)") (class "Default")
      (node (ref "J2") (pin "A17") (pinfunction "A17_A17") (pintype "passive"))
    )
    (net (code "134") (name "unconnected-(J2-PadA18)") (class "Default")
      (node (ref "J2") (pin "A18") (pinfunction "A18_A18") (pintype "passive"))
    )
    (net (code "135") (name "unconnected-(J2-PadA19)") (class "Default")
      (node (ref "J2") (pin "A19") (pinfunction "A19_A19") (pintype "passive"))
    )
    (net (code "136") (name "unconnected-(J2-PadA20)") (class "Default")
      (node (ref "J2") (pin "A20") (pinfunction "A20_A20") (pintype "passive"))
    )
    (net (code "137") (name "unconnected-(J2-PadA21)") (class "Default")
      (node (ref "J2") (pin "A21") (pinfunction "A21_A21") (pintype "passive"))
    )
    (net (code "138") (name "unconnected-(J2-PadA22)") (class "Default")
      (node (ref "J2") (pin "A22") (pinfunction "A22_A22") (pintype "passive"))
    )
    (net (code "139") (name "unconnected-(J2-PadA23)") (class "Default")
      (node (ref "J2") (pin "A23") (pinfunction "A23_A23") (pintype "passive"))
    )
    (net (code "140") (name "unconnected-(J2-PadA24)") (class "Default")
      (node (ref "J2") (pin "A24") (pinfunction "A24_A24") (pintype "passive"))
    )
    (net (code "141") (name "unconnected-(J2-PadA25)") (class "Default")
      (node (ref "J2") (pin "A25") (pinfunction "A25_A25") (pintype "passive"))
    )
    (net (code "142") (name "unconnected-(J2-PadA26)") (class "Default")
      (node (ref "J2") (pin "A26") (pinfunction "A26_A26") (pintype "passive"))
    )
    (net (code "143") (name "unconnected-(J2-PadA27)") (class "Default")
      (node (ref "J2") (pin "A27") (pinfunction "A27_A27") (pintype "passive"))
    )
    (net (code "144") (name "unconnected-(J2-PadA28)") (class "Default")
      (node (ref "J2") (pin "A28") (pinfunction "A28_A28") (pintype "passive"))
    )
    (net (code "145") (name "unconnected-(J2-PadA29)") (class "Default")
      (node (ref "J2") (pin "A29") (pinfunction "A29_A29") (pintype "passive"))
    )
    (net (code "146") (name "unconnected-(J2-PadA30)") (class "Default")
      (node (ref "J2") (pin "A30") (pinfunction "A30_A30") (pintype "passive"))
    )
    (net (code "147") (name "unconnected-(J2-PadA31)") (class "Default")
      (node (ref "J2") (pin "A31") (pinfunction "A31_A31") (pintype "passive"))
    )
    (net (code "148") (name "unconnected-(J2-PadA32)") (class "Default")
      (node (ref "J2") (pin "A32") (pinfunction "A32_A32") (pintype "passive"))
    )
    (net (code "149") (name "unconnected-(J2-PadB10)") (class "Default")
      (node (ref "J2") (pin "B10") (pinfunction "B10_B10") (pintype "passive"))
    )
    (net (code "150") (name "unconnected-(J2-PadB15)") (class "Default")
      (node (ref "J2") (pin "B15") (pinfunction "B15_B15") (pintype "passive"))
    )
    (net (code "151") (name "unconnected-(J2-PadB16)") (class "Default")
      (node (ref "J2") (pin "B16") (pinfunction "B16_B16") (pintype "passive"))
    )
    (net (code "152") (name "unconnected-(J2-PadB17)") (class "Default")
      (node (ref "J2") (pin "B17") (pinfunction "B17_B17") (pintype "passive"))
    )
    (net (code "153") (name "unconnected-(J2-PadB18)") (class "Default")
      (node (ref "J2") (pin "B18") (pinfunction "B18_B18") (pintype "passive"))
    )
    (net (code "154") (name "unconnected-(J2-PadB19)") (class "Default")
      (node (ref "J2") (pin "B19") (pinfunction "B19_B19") (pintype "passive"))
    )
    (net (code "155") (name "unconnected-(J2-PadB20)") (class "Default")
      (node (ref "J2") (pin "B20") (pinfunction "B20_B20") (pintype "passive"))
    )
    (net (code "156") (name "unconnected-(J2-PadB21)") (class "Default")
      (node (ref "J2") (pin "B21") (pinfunction "B21_B21") (pintype "passive"))
    )
    (net (code "157") (name "unconnected-(J2-PadB22)") (class "Default")
      (node (ref "J2") (pin "B22") (pinfunction "B22_B22") (pintype "passive"))
    )
    (net (code "158") (name "unconnected-(J2-PadB23)") (class "Default")
      (node (ref "J2") (pin "B23") (pinfunction "B23_B23") (pintype "passive"))
    )
    (net (code "159") (name "unconnected-(J2-PadB24)") (class "Default")
      (node (ref "J2") (pin "B24") (pinfunction "B24_B24") (pintype "passive"))
    )
    (net (code "160") (name "unconnected-(J2-PadB25)") (class "Default")
      (node (ref "J2") (pin "B25") (pinfunction "B25_B25") (pintype "passive"))
    )
    (net (code "161") (name "unconnected-(J2-PadB26)") (class "Default")
      (node (ref "J2") (pin "B26") (pinfunction "B26_B26") (pintype "passive"))
    )
    (net (code "162") (name "unconnected-(J2-PadB27)") (class "Default")
      (node (ref "J2") (pin "B27") (pinfunction "B27_B27") (pintype "passive"))
    )
    (net (code "163") (name "unconnected-(J2-PadB28)") (class "Default")
      (node (ref "J2") (pin "B28") (pinfunction "B28_B28") (pintype "passive"))
    )
    (net (code "164") (name "unconnected-(J2-PadB29)") (class "Default")
      (node (ref "J2") (pin "B29") (pinfunction "B29_B29") (pintype "passive"))
    )
    (net (code "165") (name "unconnected-(J2-PadB30)") (class "Default")
      (node (ref "J2") (pin "B30") (pinfunction "B30_B30") (pintype "passive"))
    )
    (net (code "166") (name "unconnected-(J2-PadB31)") (class "Default")
      (node (ref "J2") (pin "B31") (pinfunction "B31_B31") (pintype "passive"))
    )
    (net (code "167") (name "unconnected-(J2-PadB32)") (class "Default")
      (node (ref "J2") (pin "B32") (pinfunction "B32_B32") (pintype "passive"))
    )
    (net (code "168") (name "unconnected-(J2-PadC10)") (class "Default")
      (node (ref "J2") (pin "C10") (pinfunction "C10_C10") (pintype "passive"))
    )
    (net (code "169") (name "unconnected-(J2-PadC15)") (class "Default")
      (node (ref "J2") (pin "C15") (pinfunction "C15_C15") (pintype "passive"))
    )
    (net (code "170") (name "unconnected-(J2-PadC16)") (class "Default")
      (node (ref "J2") (pin "C16") (pinfunction "C16_C16") (pintype "passive"))
    )
    (net (code "171") (name "unconnected-(J2-PadC17)") (class "Default")
      (node (ref "J2") (pin "C17") (pinfunction "C17_C17") (pintype "passive"))
    )
    (net (code "172") (name "unconnected-(J2-PadC18)") (class "Default")
      (node (ref "J2") (pin "C18") (pinfunction "C18_C18") (pintype "passive"))
    )
    (net (code "173") (name "unconnected-(J2-PadC19)") (class "Default")
      (node (ref "J2") (pin "C19") (pinfunction "C19_C19") (pintype "passive"))
    )
    (net (code "174") (name "unconnected-(J2-PadC20)") (class "Default")
      (node (ref "J2") (pin "C20") (pinfunction "C20_C20") (pintype "passive"))
    )
    (net (code "175") (name "unconnected-(J2-PadC21)") (class "Default")
      (node (ref "J2") (pin "C21") (pinfunction "C21_C21") (pintype "passive"))
    )
    (net (code "176") (name "unconnected-(J2-PadC22)") (class "Default")
      (node (ref "J2") (pin "C22") (pinfunction "C22_C22") (pintype "passive"))
    )
    (net (code "177") (name "unconnected-(J2-PadC23)") (class "Default")
      (node (ref "J2") (pin "C23") (pinfunction "C23_C23") (pintype "passive"))
    )
    (net (code "178") (name "unconnected-(J2-PadC24)") (class "Default")
      (node (ref "J2") (pin "C24") (pinfunction "C24_C24") (pintype "passive"))
    )
    (net (code "179") (name "unconnected-(J2-PadC25)") (class "Default")
      (node (ref "J2") (pin "C25") (pinfunction "C25_C25") (pintype "passive"))
    )
    (net (code "180") (name "unconnected-(J2-PadC26)") (class "Default")
      (node (ref "J2") (pin "C26") (pinfunction "C26_C26") (pintype "passive"))
    )
    (net (code "181") (name "unconnected-(J2-PadC27)") (class "Default")
      (node (ref "J2") (pin "C27") (pinfunction "C27_C27") (pintype "passive"))
    )
    (net (code "182") (name "unconnected-(J2-PadC28)") (class "Default")
      (node (ref "J2") (pin "C28") (pinfunction "C28_C28") (pintype "passive"))
    )
    (net (code "183") (name "unconnected-(J2-PadC29)") (class "Default")
      (node (ref "J2") (pin "C29") (pinfunction "C29_C29") (pintype "passive"))
    )
    (net (code "184") (name "unconnected-(J2-PadC30)") (class "Default")
      (node (ref "J2") (pin "C30") (pinfunction "C30_C30") (pintype "passive"))
    )
    (net (code "185") (name "unconnected-(J2-PadC31)") (class "Default")
      (node (ref "J2") (pin "C31") (pinfunction "C31_C31") (pintype "passive"))
    )
    (net (code "186") (name "unconnected-(J2-PadC32)") (class "Default")
      (node (ref "J2") (pin "C32") (pinfunction "C32_C32") (pintype "passive"))
    )
    (net (code "187") (name "unconnected-(JP1-Pad6)") (class "Default")
      (node (ref "JP1") (pin "6") (pinfunction "6_6") (pintype "passive"))
    )
    (net (code "188") (name "unconnected-(JP2-Pad6)") (class "Default")
      (node (ref "JP2") (pin "6") (pinfunction "6_6") (pintype "passive"))
    )
    (net (code "189") (name "unconnected-(PIC16-Pad2)") (class "Default")
      (node (ref "PIC16") (pin "2") (pinfunction "2_2") (pintype "passive"))
    )
    (net (code "190") (name "unconnected-(PIC16-Pad3)") (class "Default")
      (node (ref "PIC16") (pin "3") (pinfunction "3_3") (pintype "passive"))
    )
    (net (code "191") (name "unconnected-(PIC16-Pad11)") (class "Default")
      (node (ref "PIC16") (pin "11") (pinfunction "11_11") (pintype "passive"))
    )
    (net (code "192") (name "unconnected-(PIC16-Pad13)") (class "Default")
      (node (ref "PIC16") (pin "13") (pinfunction "13_13") (pintype "passive"))
    )
    (net (code "193") (name "unconnected-(U$1-CLK-Pad6)") (class "Default")
      (node (ref "U$1") (pin "6") (pinfunction "CLK_6") (pintype "bidirectional"))
    )
    (net (code "194") (name "unconnected-(U$1-CS-Pad5)") (class "Default")
      (node (ref "U$1") (pin "5") (pinfunction "CS_5") (pintype "bidirectional"))
    )
    (net (code "195") (name "unconnected-(U$1-GND2-Pad15)") (class "Default")
      (node (ref "U$1") (pin "15") (pinfunction "GND2_15") (pintype "bidirectional"))
    )
    (net (code "196") (name "unconnected-(U$1-MISO-Pad7)") (class "Default")
      (node (ref "U$1") (pin "7") (pinfunction "MISO_7") (pintype "bidirectional"))
    )
    (net (code "197") (name "unconnected-(U$1-MOSI-Pad8)") (class "Default")
      (node (ref "U$1") (pin "8") (pinfunction "MOSI_8") (pintype "bidirectional"))
    )
    (net (code "198") (name "unconnected-(U$1-NAV-Pad14)") (class "Default")
      (node (ref "U$1") (pin "14") (pinfunction "NAV_14") (pintype "bidirectional"))
    )
    (net (code "199") (name "unconnected-(U$1-PPS-Pad13)") (class "Default")
      (node (ref "U$1") (pin "13") (pinfunction "PPS_13") (pintype "bidirectional"))
    )
    (net (code "200") (name "unconnected-(U$1-RX1-Pad12)") (class "Default")
      (node (ref "U$1") (pin "12") (pinfunction "RX1_12") (pintype "bidirectional"))
    )
    (net (code "201") (name "unconnected-(U$1-SCL-Pad10)") (class "Default")
      (node (ref "U$1") (pin "10") (pinfunction "SCL_10") (pintype "bidirectional"))
    )
    (net (code "202") (name "unconnected-(U$1-SDA-Pad9)") (class "Default")
      (node (ref "U$1") (pin "9") (pinfunction "SDA_9") (pintype "bidirectional"))
    )
    (net (code "203") (name "unconnected-(U$1-TX1-Pad11)") (class "Default")
      (node (ref "U$1") (pin "11") (pinfunction "TX1_11") (pintype "bidirectional"))
    )
    (net (code "204") (name "unconnected-(U$1-VBAT-Pad16)") (class "Default")
      (node (ref "U$1") (pin "16") (pinfunction "VBAT_16") (pintype "bidirectional"))
    )
    (net (code "205") (name "unconnected-(X1-Pad14)") (class "Default")
      (node (ref "X1") (pin "14") (pinfunction "14_14") (pintype "passive"))
    )
    (net (code "206") (name "unconnected-(X1-Pad15)") (class "Default")
      (node (ref "X1") (pin "15") (pinfunction "15_15") (pintype "passive"))
    )
    (net (code "207") (name "unconnected-(X2-Pad3)") (class "Default")
      (node (ref "X2") (pin "3") (pinfunction "3_3") (pintype "passive"))
    )
    (net (code "208") (name "unconnected-(X2-Pad7)") (class "Default")
      (node (ref "X2") (pin "7") (pinfunction "7_7") (pintype "passive"))
    )
    (net (code "209") (name "unconnected-(X2-Pad10)") (class "Default")
      (node (ref "X2") (pin "10") (pinfunction "10_10") (pintype "passive"))
    )
    (net (code "210") (name "unconnected-(X2-Pad11)") (class "Default")
      (node (ref "X2") (pin "11") (pinfunction "11_11") (pintype "passive"))
    )
  )
)
